# OPT_4ch.net
KiCad netlist of a schematic drawn in EAGLE
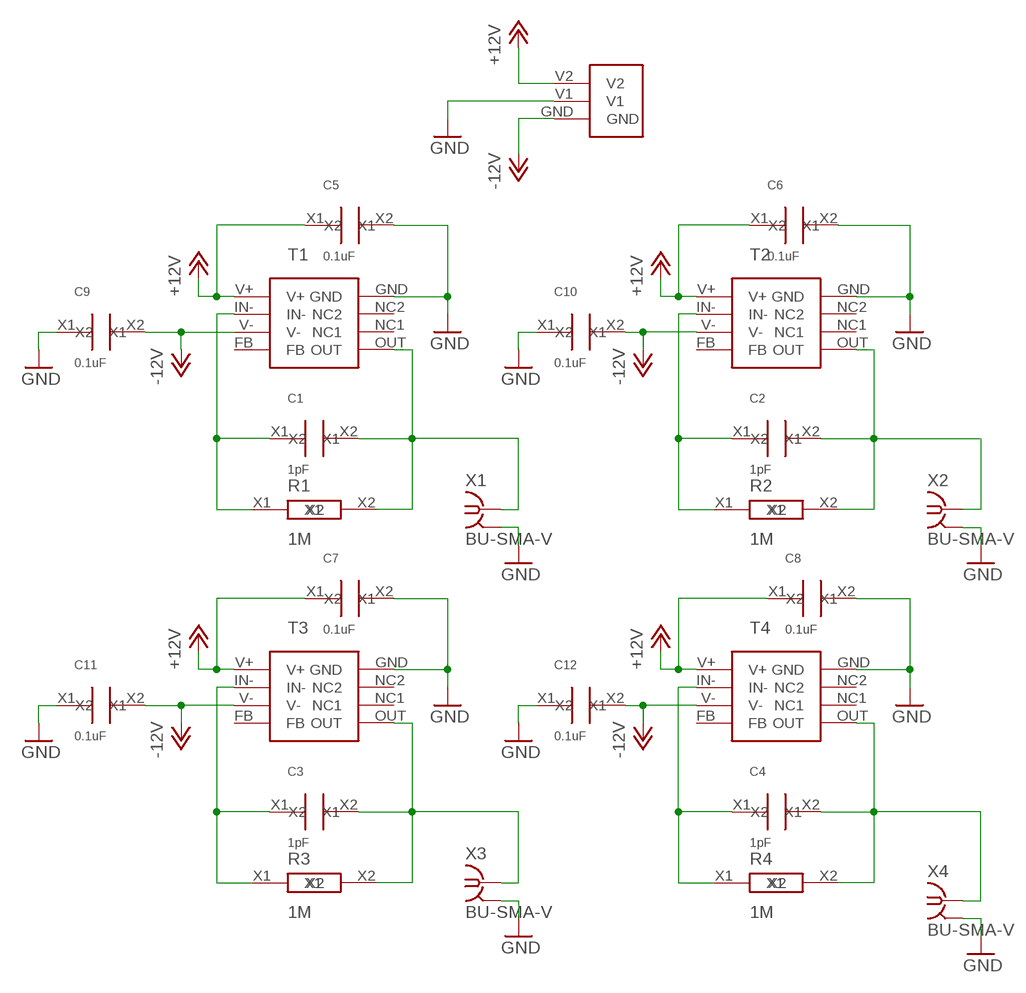
[diagram p0: schematic, sheet 1]

(export (version "E")
  (design (tool "Eeschema 10.0.6"))
  (components
    (comp (ref "C1")
      (value "1pF")
      (footprint "eagle-import:SMD_2.1X1.25")
      (libsource (lib "eagle-import") (part "C_SMD_2.1X1.25"))
    )
    (comp (ref "C2")
      (value "1pF")
      (footprint "eagle-import:SMD_2.1X1.25")
      (libsource (lib "eagle-import") (part "C_SMD_2.1X1.25"))
    )
    (comp (ref "C3")
      (value "1pF")
      (footprint "eagle-import:SMD_2.1X1.25")
      (libsource (lib "eagle-import") (part "C_SMD_2.1X1.25"))
    )
    (comp (ref "C4")
      (value "1pF")
      (footprint "eagle-import:SMD_2.1X1.25")
      (libsource (lib "eagle-import") (part "C_SMD_2.1X1.25"))
    )
    (comp (ref "C5")
      (value "0.1uF")
      (footprint "eagle-import:SMD_2.1X1.25")
      (libsource (lib "eagle-import") (part "C_SMD_2.1X1.25"))
    )
    (comp (ref "C6")
      (value "0.1uF")
      (footprint "eagle-import:SMD_2.1X1.25")
      (libsource (lib "eagle-import") (part "C_SMD_2.1X1.25"))
    )
    (comp (ref "C7")
      (value "0.1uF")
      (footprint "eagle-import:SMD_2.1X1.25")
      (libsource (lib "eagle-import") (part "C_SMD_2.1X1.25"))
    )
    (comp (ref "C8")
      (value "0.1uF")
      (footprint "eagle-import:SMD_2.1X1.25")
      (libsource (lib "eagle-import") (part "C_SMD_2.1X1.25"))
    )
    (comp (ref "C9")
      (value "0.1uF")
      (footprint "eagle-import:SMD_2.1X1.25")
      (libsource (lib "eagle-import") (part "C_SMD_2.1X1.25"))
    )
    (comp (ref "C10")
      (value "0.1uF")
      (footprint "eagle-import:SMD_2.1X1.25")
      (libsource (lib "eagle-import") (part "C_SMD_2.1X1.25"))
    )
    (comp (ref "C11")
      (value "0.1uF")
      (footprint "eagle-import:SMD_2.1X1.25")
      (libsource (lib "eagle-import") (part "C_SMD_2.1X1.25"))
    )
    (comp (ref "C12")
      (value "0.1uF")
      (footprint "eagle-import:SMD_2.1X1.25")
      (libsource (lib "eagle-import") (part "C_SMD_2.1X1.25"))
    )
    (comp (ref "R1")
      (value "1M")
      (footprint "eagle-import:SMD_2.1X1.25")
      (libsource (lib "eagle-import") (part "R_SMD_2.1X1.25"))
    )
    (comp (ref "R2")
      (value "1M")
      (footprint "eagle-import:SMD_2.1X1.25")
      (libsource (lib "eagle-import") (part "R_SMD_2.1X1.25"))
    )
    (comp (ref "R3")
      (value "1M")
      (footprint "eagle-import:SMD_2.1X1.25")
      (libsource (lib "eagle-import") (part "R_SMD_2.1X1.25"))
    )
    (comp (ref "R4")
      (value "1M")
      (footprint "eagle-import:SMD_2.1X1.25")
      (libsource (lib "eagle-import") (part "R_SMD_2.1X1.25"))
    )
    (comp (ref "T1")
      (value "OPT101")
      (footprint "eagle-import:OPT101")
      (libsource (lib "eagle-import") (part "OPT101"))
    )
    (comp (ref "T2")
      (value "OPT101")
      (footprint "eagle-import:OPT101")
      (libsource (lib "eagle-import") (part "OPT101"))
    )
    (comp (ref "T3")
      (value "OPT101")
      (footprint "eagle-import:OPT101")
      (libsource (lib "eagle-import") (part "OPT101"))
    )
    (comp (ref "T4")
      (value "OPT101")
      (footprint "eagle-import:OPT101")
      (libsource (lib "eagle-import") (part "OPT101"))
    )
    (comp (ref "U$1")
      (value "BAT3_PLUG")
      (footprint "eagle-import:BAT3_PLUG")
      (libsource (lib "eagle-import") (part "BAT3_PLUG"))
    )
    (comp (ref "X1")
      (value "BU-SMA-V")
      (footprint "eagle-import:BU-SMA-V")
      (libsource (lib "eagle-import") (part "BU-SMA-V"))
    )
    (comp (ref "X2")
      (value "BU-SMA-V")
      (footprint "eagle-import:BU-SMA-V")
      (libsource (lib "eagle-import") (part "BU-SMA-V"))
    )
    (comp (ref "X3")
      (value "BU-SMA-V")
      (footprint "eagle-import:BU-SMA-V")
      (libsource (lib "eagle-import") (part "BU-SMA-V"))
    )
    (comp (ref "X4")
      (value "BU-SMA-V")
      (footprint "eagle-import:BU-SMA-V")
      (libsource (lib "eagle-import") (part "BU-SMA-V"))
    )
  )
  (nets
    (net (code "1") (name "+12V") (class "Default")
      (node (ref "C5") (pin "X1") (pinfunction "X1_X1") (pintype "bidirectional"))
      (node (ref "C6") (pin "X1") (pinfunction "X1_X1") (pintype "bidirectional"))
      (node (ref "C7") (pin "X1") (pinfunction "X1_X1") (pintype "bidirectional"))
      (node (ref "C8") (pin "X1") (pinfunction "X1_X1") (pintype "bidirectional"))
      (node (ref "T1") (pin "V+") (pinfunction "V+_V+") (pintype "bidirectional"))
      (node (ref "T2") (pin "V+") (pinfunction "V+_V+") (pintype "bidirectional"))
      (node (ref "T3") (pin "V+") (pinfunction "V+_V+") (pintype "bidirectional"))
      (node (ref "T4") (pin "V+") (pinfunction "V+_V+") (pintype "bidirectional"))
      (node (ref "U$1") (pin "V2") (pinfunction "V2_V2") (pintype "bidirectional"))
    )
    (net (code "2") (name "-12V") (class "Default")
      (node (ref "C10") (pin "X2") (pinfunction "X2_X2") (pintype "bidirectional"))
      (node (ref "C11") (pin "X2") (pinfunction "X2_X2") (pintype "bidirectional"))
      (node (ref "C12") (pin "X2") (pinfunction "X2_X2") (pintype "bidirectional"))
      (node (ref "C9") (pin "X2") (pinfunction "X2_X2") (pintype "bidirectional"))
      (node (ref "T1") (pin "V-") (pinfunction "V-_V-") (pintype "bidirectional"))
      (node (ref "T2") (pin "V-") (pinfunction "V-_V-") (pintype "bidirectional"))
      (node (ref "T3") (pin "V-") (pinfunction "V-_V-") (pintype "bidirectional"))
      (node (ref "T4") (pin "V-") (pinfunction "V-_V-") (pintype "bidirectional"))
      (node (ref "U$1") (pin "GND") (pinfunction "GND_GND") (pintype "bidirectional"))
    )
    (net (code "3") (name "GND") (class "Default")
      (node (ref "C10") (pin "X1") (pinfunction "X1_X1") (pintype "bidirectional"))
      (node (ref "C11") (pin "X1") (pinfunction "X1_X1") (pintype "bidirectional"))
      (node (ref "C12") (pin "X1") (pinfunction "X1_X1") (pintype "bidirectional"))
      (node (ref "C5") (pin "X2") (pinfunction "X2_X2") (pintype "bidirectional"))
      (node (ref "C6") (pin "X2") (pinfunction "X2_X2") (pintype "bidirectional"))
      (node (ref "C7") (pin "X2") (pinfunction "X2_X2") (pintype "bidirectional"))
      (node (ref "C8") (pin "X2") (pinfunction "X2_X2") (pintype "bidirectional"))
      (node (ref "C9") (pin "X1") (pinfunction "X1_X1") (pintype "bidirectional"))
      (node (ref "T1") (pin "GND") (pinfunction "GND_GND") (pintype "bidirectional"))
      (node (ref "T2") (pin "GND") (pinfunction "GND_GND") (pintype "bidirectional"))
      (node (ref "T3") (pin "GND") (pinfunction "GND_GND") (pintype "bidirectional"))
      (node (ref "T4") (pin "GND") (pinfunction "GND_GND") (pintype "bidirectional"))
      (node (ref "U$1") (pin "V1") (pinfunction "V1_V1") (pintype "bidirectional"))
      (node (ref "X1") (pin "2") (pinfunction "2_2") (pintype "passive"))
      (node (ref "X1") (pin "3") (pinfunction "2_3") (pintype "passive"))
      (node (ref "X1") (pin "4") (pinfunction "2_4") (pintype "passive"))
      (node (ref "X1") (pin "5") (pinfunction "2_5") (pintype "passive"))
      (node (ref "X2") (pin "2") (pinfunction "2_2") (pintype "passive"))
      (node (ref "X2") (pin "3") (pinfunction "2_3") (pintype "passive"))
      (node (ref "X2") (pin "4") (pinfunction "2_4") (pintype "passive"))
      (node (ref "X2") (pin "5") (pinfunction "2_5") (pintype "passive"))
      (node (ref "X3") (pin "2") (pinfunction "2_2") (pintype "passive"))
      (node (ref "X3") (pin "3") (pinfunction "2_3") (pintype "passive"))
      (node (ref "X3") (pin "4") (pinfunction "2_4") (pintype "passive"))
      (node (ref "X3") (pin "5") (pinfunction "2_5") (pintype "passive"))
      (node (ref "X4") (pin "2") (pinfunction "2_2") (pintype "passive"))
      (node (ref "X4") (pin "3") (pinfunction "2_3") (pintype "passive"))
      (node (ref "X4") (pin "4") (pinfunction "2_4") (pintype "passive"))
      (node (ref "X4") (pin "5") (pinfunction "2_5") (pintype "passive"))
    )
    (net (code "4") (name "Net-(C1-PadX1)") (class "Default")
      (node (ref "C1") (pin "X1") (pinfunction "X1_X1") (pintype "bidirectional"))
      (node (ref "R1") (pin "X1") (pinfunction "X1_X1") (pintype "bidirectional"))
      (node (ref "T1") (pin "IN-") (pinfunction "IN-_IN-") (pintype "bidirectional"))
    )
    (net (code "5") (name "Net-(C1-PadX2)") (class "Default")
      (node (ref "C1") (pin "X2") (pinfunction "X2_X2") (pintype "bidirectional"))
      (node (ref "R1") (pin "X2") (pinfunction "X2_X2") (pintype "bidirectional"))
      (node (ref "T1") (pin "OUT") (pinfunction "OUT_OUT") (pintype "bidirectional"))
      (node (ref "X1") (pin "1") (pinfunction "1_1") (pintype "passive"))
    )
    (net (code "6") (name "Net-(C2-PadX1)") (class "Default")
      (node (ref "C2") (pin "X1") (pinfunction "X1_X1") (pintype "bidirectional"))
      (node (ref "R2") (pin "X1") (pinfunction "X1_X1") (pintype "bidirectional"))
      (node (ref "T2") (pin "IN-") (pinfunction "IN-_IN-") (pintype "bidirectional"))
    )
    (net (code "7") (name "Net-(C2-PadX2)") (class "Default")
      (node (ref "C2") (pin "X2") (pinfunction "X2_X2") (pintype "bidirectional"))
      (node (ref "R2") (pin "X2") (pinfunction "X2_X2") (pintype "bidirectional"))
      (node (ref "T2") (pin "OUT") (pinfunction "OUT_OUT") (pintype "bidirectional"))
      (node (ref "X2") (pin "1") (pinfunction "1_1") (pintype "passive"))
    )
    (net (code "8") (name "Net-(C3-PadX1)") (class "Default")
      (node (ref "C3") (pin "X1") (pinfunction "X1_X1") (pintype "bidirectional"))
      (node (ref "R3") (pin "X1") (pinfunction "X1_X1") (pintype "bidirectional"))
      (node (ref "T3") (pin "IN-") (pinfunction "IN-_IN-") (pintype "bidirectional"))
    )
    (net (code "9") (name "Net-(C3-PadX2)") (class "Default")
      (node (ref "C3") (pin "X2") (pinfunction "X2_X2") (pintype "bidirectional"))
      (node (ref "R3") (pin "X2") (pinfunction "X2_X2") (pintype "bidirectional"))
      (node (ref "T3") (pin "OUT") (pinfunction "OUT_OUT") (pintype "bidirectional"))
      (node (ref "X3") (pin "1") (pinfunction "1_1") (pintype "passive"))
    )
    (net (code "10") (name "Net-(C4-PadX1)") (class "Default")
      (node (ref "C4") (pin "X1") (pinfunction "X1_X1") (pintype "bidirectional"))
      (node (ref "R4") (pin "X1") (pinfunction "X1_X1") (pintype "bidirectional"))
      (node (ref "T4") (pin "IN-") (pinfunction "IN-_IN-") (pintype "bidirectional"))
    )
    (net (code "11") (name "Net-(C4-PadX2)") (class "Default")
      (node (ref "C4") (pin "X2") (pinfunction "X2_X2") (pintype "bidirectional"))
      (node (ref "R4") (pin "X2") (pinfunction "X2_X2") (pintype "bidirectional"))
      (node (ref "T4") (pin "OUT") (pinfunction "OUT_OUT") (pintype "bidirectional"))
      (node (ref "X4") (pin "1") (pinfunction "1_1") (pintype "passive"))
    )
    (net (code "12") (name "unconnected-(T1-PadFB)") (class "Default")
      (node (ref "T1") (pin "FB") (pinfunction "FB_FB") (pintype "bidirectional"))
    )
    (net (code "13") (name "unconnected-(T1-PadNC1)") (class "Default")
      (node (ref "T1") (pin "NC1") (pinfunction "NC1_NC1") (pintype "bidirectional"))
    )
    (net (code "14") (name "unconnected-(T1-PadNC2)") (class "Default")
      (node (ref "T1") (pin "NC2") (pinfunction "NC2_NC2") (pintype "bidirectional"))
    )
    (net (code "15") (name "unconnected-(T2-PadFB)") (class "Default")
      (node (ref "T2") (pin "FB") (pinfunction "FB_FB") (pintype "bidirectional"))
    )
    (net (code "16") (name "unconnected-(T2-PadNC1)") (class "Default")
      (node (ref "T2") (pin "NC1") (pinfunction "NC1_NC1") (pintype "bidirectional"))
    )
    (net (code "17") (name "unconnected-(T2-PadNC2)") (class "Default")
      (node (ref "T2") (pin "NC2") (pinfunction "NC2_NC2") (pintype "bidirectional"))
    )
    (net (code "18") (name "unconnected-(T3-PadFB)") (class "Default")
      (node (ref "T3") (pin "FB") (pinfunction "FB_FB") (pintype "bidirectional"))
    )
    (net (code "19") (name "unconnected-(T3-PadNC1)") (class "Default")
      (node (ref "T3") (pin "NC1") (pinfunction "NC1_NC1") (pintype "bidirectional"))
    )
    (net (code "20") (name "unconnected-(T3-PadNC2)") (class "Default")
      (node (ref "T3") (pin "NC2") (pinfunction "NC2_NC2") (pintype "bidirectional"))
    )
    (net (code "21") (name "unconnected-(T4-PadFB)") (class "Default")
      (node (ref "T4") (pin "FB") (pinfunction "FB_FB") (pintype "bidirectional"))
    )
    (net (code "22") (name "unconnected-(T4-PadNC1)") (class "Default")
      (node (ref "T4") (pin "NC1") (pinfunction "NC1_NC1") (pintype "bidirectional"))
    )
    (net (code "23") (name "unconnected-(T4-PadNC2)") (class "Default")
      (node (ref "T4") (pin "NC2") (pinfunction "NC2_NC2") (pintype "bidirectional"))
    )
  )
)
